# lipo_charger.net
KiCad netlist of a schematic drawn in EAGLE
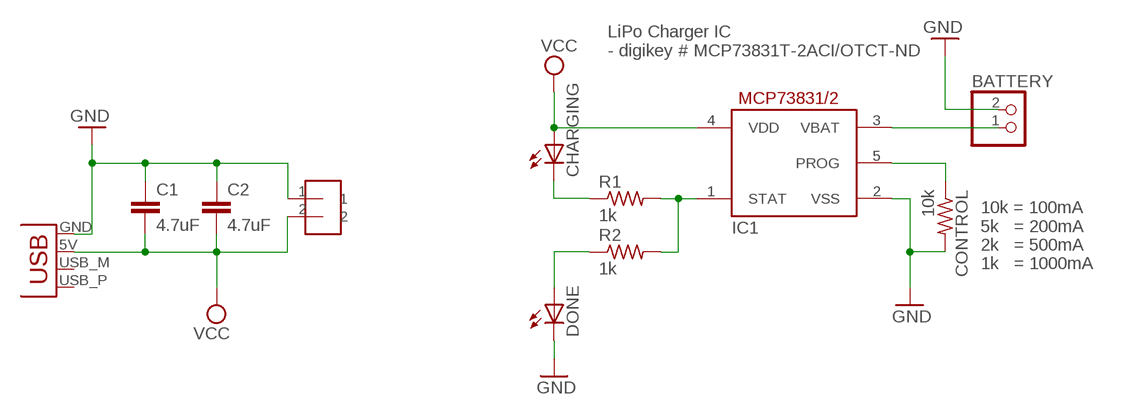
[diagram p0: schematic, sheet 1]

(export (version "E")
  (design (tool "Eeschema 10.0.6"))
  (components
    (comp (ref "BATTERY")
      (value "JST_2PIN-SMT-RA")
      (footprint "eagle-import:JST-PH-2-SMT-RA")
      (libsource (lib "eagle-import") (part "JST_2PIN-SMT-RA"))
    )
    (comp (ref "C1")
      (value "4.7uF")
      (footprint "eagle-import:0603-CAP")
      (libsource (lib "eagle-import") (part "CAP0603-CAP"))
    )
    (comp (ref "C2")
      (value "4.7uF")
      (footprint "eagle-import:0603-CAP")
      (libsource (lib "eagle-import") (part "CAP0603-CAP"))
    )
    (comp (ref "CHARGING")
      (value "LEDCHIPLED_0603")
      (footprint "eagle-import:CHIPLED_0603")
      (libsource (lib "eagle-import") (part "LEDCHIPLED_0603"))
    )
    (comp (ref "CONTROL")
      (value "10k")
      (footprint "eagle-import:R0603")
      (libsource (lib "eagle-import") (part "R-US_R0603"))
    )
    (comp (ref "DONE")
      (value "LEDCHIPLED_0603")
      (footprint "eagle-import:CHIPLED_0603")
      (libsource (lib "eagle-import") (part "LEDCHIPLED_0603"))
    )
    (comp (ref "IC1")
      (value "MCP73831/OT")
      (footprint "eagle-import:SOT23-5L")
      (libsource (lib "eagle-import") (part "MCP73831/OT"))
    )
    (comp (ref "JP1")
      (value "USBPCB")
      (footprint "eagle-import:USB-A-PCB")
      (libsource (lib "eagle-import") (part "USBPCB"))
    )
    (comp (ref "R1")
      (value "1k")
      (footprint "eagle-import:R0603")
      (libsource (lib "eagle-import") (part "R-US_R0603"))
    )
    (comp (ref "R2")
      (value "1k")
      (footprint "eagle-import:R0603")
      (libsource (lib "eagle-import") (part "R-US_R0603"))
    )
    (comp (ref "U$1")
      (value "HEADER-2")
      (footprint "eagle-import:HEADER-2")
      (libsource (lib "eagle-import") (part "HEADER-2"))
    )
  )
  (nets
    (net (code "1") (name "GND") (class "Default")
      (node (ref "BATTERY") (pin "2") (pinfunction "1_2") (pintype "passive"))
      (node (ref "C1") (pin "1") (pinfunction "1_1") (pintype "passive"))
      (node (ref "C2") (pin "1") (pinfunction "1_1") (pintype "passive"))
      (node (ref "CONTROL") (pin "2") (pinfunction "2_2") (pintype "passive"))
      (node (ref "DONE") (pin "C") (pinfunction "C_C") (pintype "passive"))
      (node (ref "IC1") (pin "2") (pinfunction "VSS_2") (pintype "power_in"))
      (node (ref "JP1") (pin "GND") (pinfunction "GND_GND") (pintype "bidirectional"))
      (node (ref "U$1") (pin "1") (pinfunction "1_1") (pintype "bidirectional"))
    )
    (net (code "2") (name "Net-(BATTERY-2)") (class "Default")
      (node (ref "BATTERY") (pin "1") (pinfunction "2_1") (pintype "passive"))
      (node (ref "IC1") (pin "3") (pinfunction "VBAT_3") (pintype "bidirectional"))
    )
    (net (code "3") (name "Net-(CHARGING-PadC)") (class "Default")
      (node (ref "CHARGING") (pin "C") (pinfunction "C_C") (pintype "passive"))
      (node (ref "R1") (pin "1") (pinfunction "1_1") (pintype "passive"))
    )
    (net (code "4") (name "Net-(DONE-PadA)") (class "Default")
      (node (ref "DONE") (pin "A") (pinfunction "A_A") (pintype "passive"))
      (node (ref "R2") (pin "1") (pinfunction "1_1") (pintype "passive"))
    )
    (net (code "5") (name "Net-(IC1-PROG)") (class "Default")
      (node (ref "CONTROL") (pin "1") (pinfunction "1_1") (pintype "passive"))
      (node (ref "IC1") (pin "5") (pinfunction "PROG_5") (pintype "input"))
    )
    (net (code "6") (name "Net-(IC1-STAT)") (class "Default")
      (node (ref "IC1") (pin "1") (pinfunction "STAT_1") (pintype "output"))
      (node (ref "R1") (pin "2") (pinfunction "2_2") (pintype "passive"))
      (node (ref "R2") (pin "2") (pinfunction "2_2") (pintype "passive"))
    )
    (net (code "7") (name "VCC") (class "Default")
      (node (ref "C1") (pin "2") (pinfunction "2_2") (pintype "passive"))
      (node (ref "C2") (pin "2") (pinfunction "2_2") (pintype "passive"))
      (node (ref "CHARGING") (pin "A") (pinfunction "A_A") (pintype "passive"))
      (node (ref "IC1") (pin "4") (pinfunction "VDD_4") (pintype "power_in"))
      (node (ref "JP1") (pin "5V") (pinfunction "VBUS_5V") (pintype "bidirectional"))
      (node (ref "U$1") (pin "2") (pinfunction "2_2") (pintype "bidirectional"))
    )
    (net (code "8") (name "unconnected-(JP1-D+-PadUSB_P)") (class "Default")
      (node (ref "JP1") (pin "USB_P") (pinfunction "D+_USB_P") (pintype "bidirectional"))
    )
    (net (code "9") (name "unconnected-(JP1-D--PadUSB_M)") (class "Default")
      (node (ref "JP1") (pin "USB_M") (pinfunction "D-_USB_M") (pintype "bidirectional"))
    )
  )
)
